# iiitduino_copy.net
KiCad netlist of a schematic drawn in EAGLE
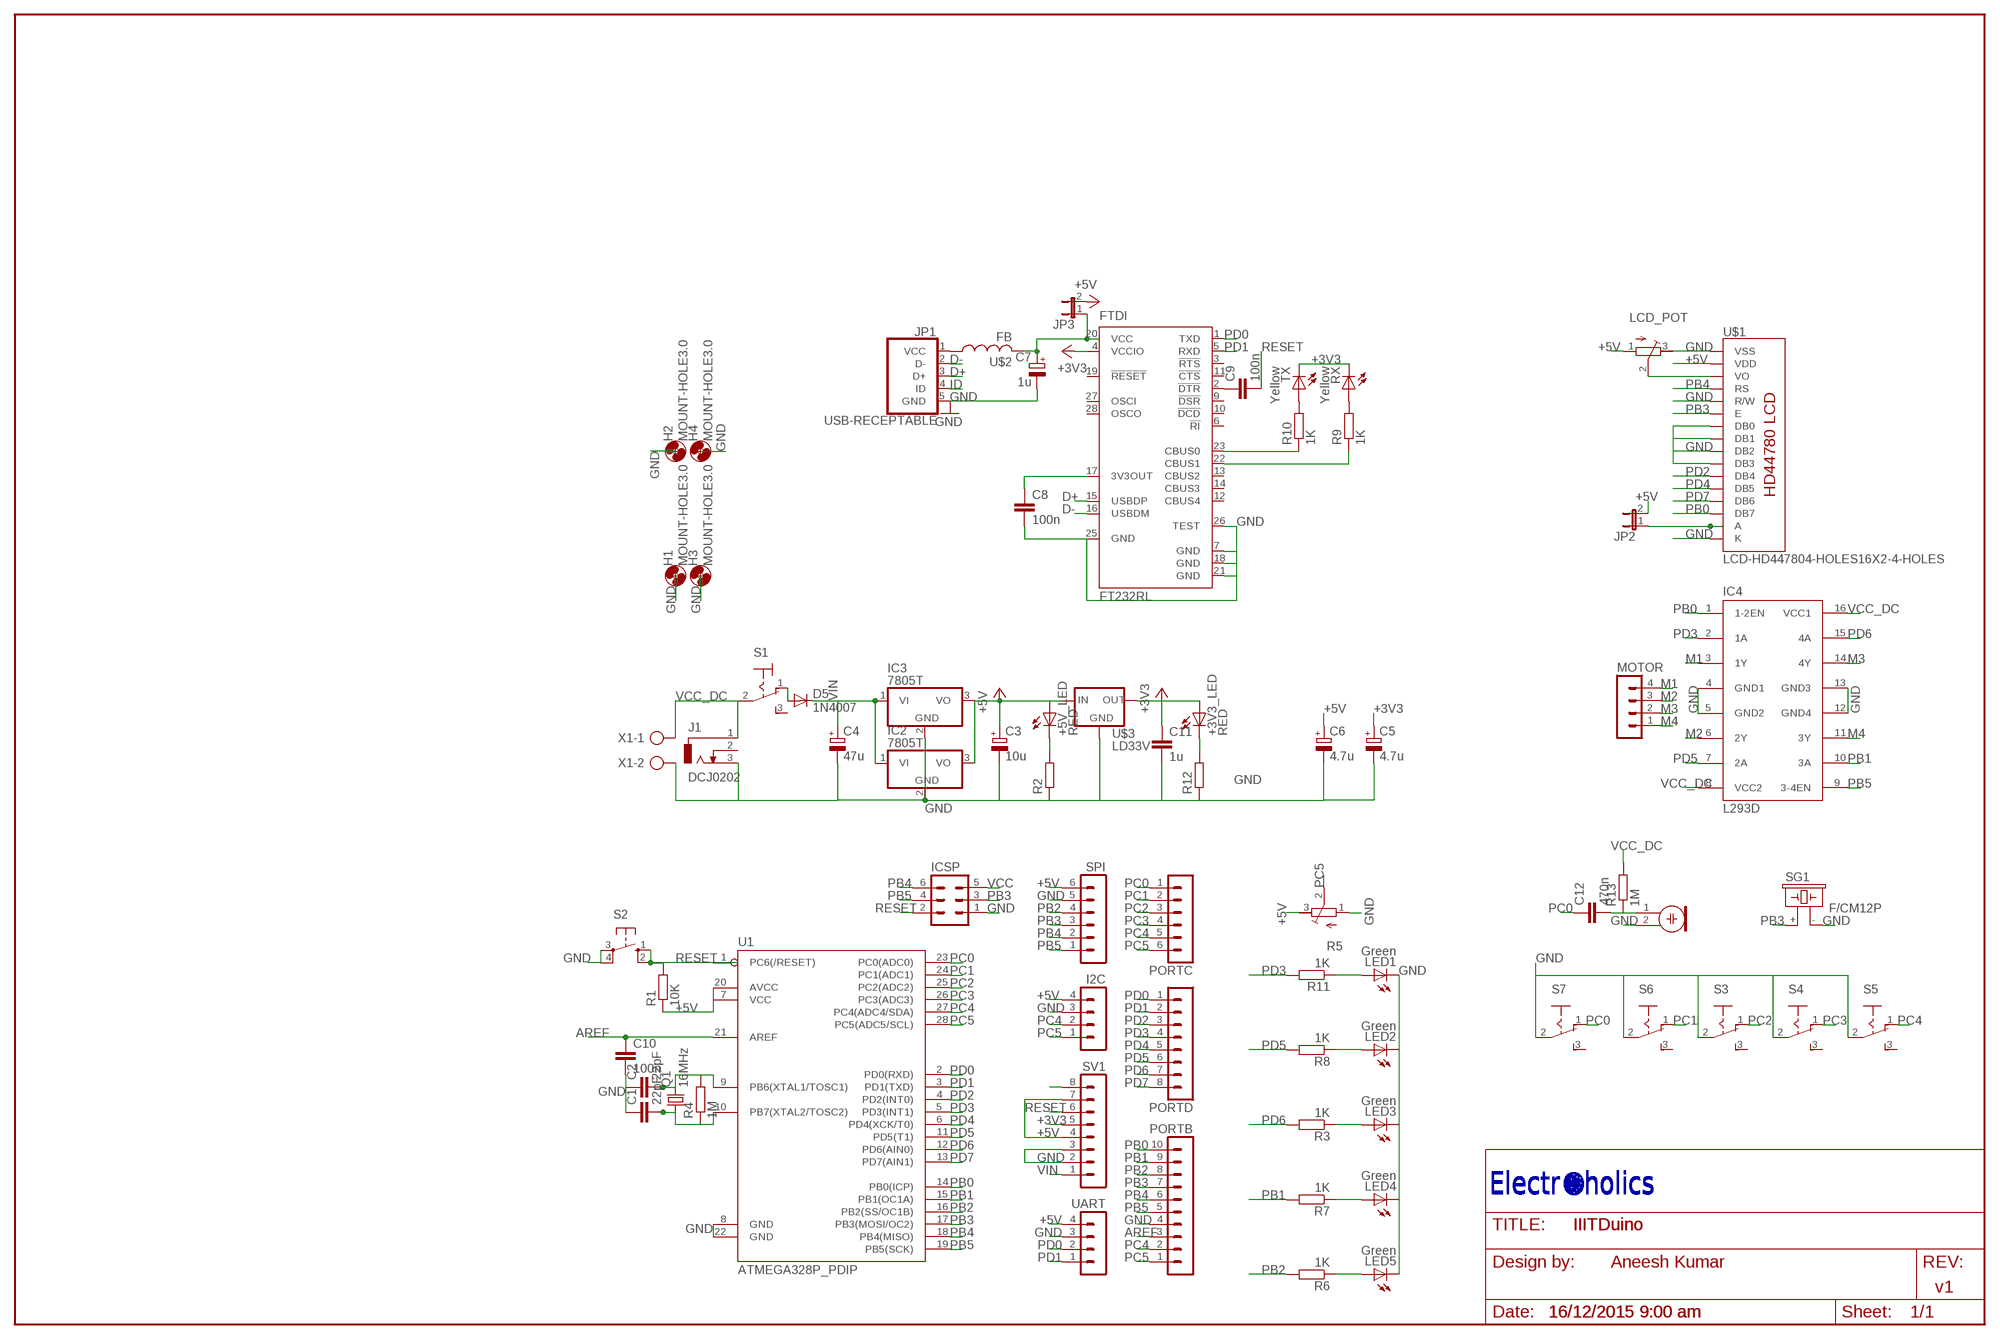
[diagram p0: schematic, sheet 1]

(export (version "E")
  (design (tool "Eeschema 10.0.6"))
  (components
    (comp (ref "+3V3_LED")
      (value "RED")
      (footprint "eagle-import:LED3MM")
      (libsource (lib "eagle-import") (part "LED3MM"))
    )
    (comp (ref "+5V_LED")
      (value "RED")
      (footprint "eagle-import:LED3MM")
      (libsource (lib "eagle-import") (part "LED3MM"))
    )
    (comp (ref "C1")
      (value "22pF")
      (footprint "eagle-import:C025-025X050")
      (libsource (lib "eagle-import") (part "C-EU025-025X050"))
    )
    (comp (ref "C2")
      (value "22pF")
      (footprint "eagle-import:C025-025X050")
      (libsource (lib "eagle-import") (part "C-EU025-025X050"))
    )
    (comp (ref "C3")
      (value "10u")
      (footprint "eagle-import:E2,5-6")
      (libsource (lib "eagle-import") (part "CPOL-EUE2.5-6"))
    )
    (comp (ref "C4")
      (value "47u")
      (footprint "eagle-import:E5-10,5")
      (libsource (lib "eagle-import") (part "CPOL-EUE5-10.5"))
    )
    (comp (ref "C5")
      (value "4.7u")
      (footprint "eagle-import:E2,5-6")
      (libsource (lib "eagle-import") (part "CPOL-EUE2.5-6"))
    )
    (comp (ref "C6")
      (value "4.7u")
      (footprint "eagle-import:E2,5-6")
      (libsource (lib "eagle-import") (part "CPOL-EUE2.5-6"))
    )
    (comp (ref "C7")
      (value "1u")
      (footprint "eagle-import:E2,5-6")
      (libsource (lib "eagle-import") (part "CPOL-EUE2.5-6"))
    )
    (comp (ref "C8")
      (value "100n")
      (footprint "eagle-import:C025-025X050")
      (libsource (lib "eagle-import") (part "C-EU025-025X050"))
    )
    (comp (ref "C9")
      (value "100n")
      (footprint "eagle-import:C025-025X050")
      (libsource (lib "eagle-import") (part "C-EU025-025X050"))
    )
    (comp (ref "C10")
      (value "100n")
      (footprint "eagle-import:C025-025X050")
      (libsource (lib "eagle-import") (part "C-EU025-025X050"))
    )
    (comp (ref "C11")
      (value "1u")
      (footprint "eagle-import:C025-025X050")
      (libsource (lib "eagle-import") (part "C-EU025-025X050"))
    )
    (comp (ref "C12")
      (value "470n")
      (footprint "eagle-import:C025-025X050")
      (libsource (lib "eagle-import") (part "C-EU025-025X050"))
    )
    (comp (ref "D5")
      (value "1N4007")
      (footprint "eagle-import:DO41-10")
      (libsource (lib "eagle-import") (part "1N4004"))
    )
    (comp (ref "FTDI")
      (value "FT232RL")
      (footprint "eagle-import:SSOP28")
      (libsource (lib "eagle-import") (part "FT232RL"))
    )
    (comp (ref "H1")
      (value "MOUNT-HOLE3.0")
      (footprint "eagle-import:3,0")
      (libsource (lib "eagle-import") (part "MOUNT-HOLE3.0"))
    )
    (comp (ref "H2")
      (value "MOUNT-HOLE3.0")
      (footprint "eagle-import:3,0")
      (libsource (lib "eagle-import") (part "MOUNT-HOLE3.0"))
    )
    (comp (ref "H3")
      (value "MOUNT-HOLE3.0")
      (footprint "eagle-import:3,0")
      (libsource (lib "eagle-import") (part "MOUNT-HOLE3.0"))
    )
    (comp (ref "H4")
      (value "MOUNT-HOLE3.0")
      (footprint "eagle-import:3,0")
      (libsource (lib "eagle-import") (part "MOUNT-HOLE3.0"))
    )
    (comp (ref "I2C")
      (value "MA04-1")
      (footprint "eagle-import:MA04-1")
      (libsource (lib "eagle-import") (part "MA04-1"))
    )
    (comp (ref "IC2")
      (value "7805T")
      (footprint "eagle-import:TO220H")
      (libsource (lib "eagle-import") (part "78T05"))
    )
    (comp (ref "IC3")
      (value "7805T")
      (footprint "eagle-import:TO220H")
      (libsource (lib "eagle-import") (part "78T05"))
    )
    (comp (ref "IC4")
      (value "L293D")
      (footprint "eagle-import:DIL16")
      (libsource (lib "eagle-import") (part "L293D"))
    )
    (comp (ref "ICSP")
      (value "MA03-2")
      (footprint "eagle-import:MA03-2")
      (libsource (lib "eagle-import") (part "MA03-2"))
    )
    (comp (ref "J1")
      (value "DCJ0202")
      (footprint "eagle-import:DCJ0202")
      (libsource (lib "eagle-import") (part "DCJ0202"))
    )
    (comp (ref "JP1")
      (value "USB-RECEPTABLE")
      (footprint "eagle-import:FCI-10103594-0001LF")
      (libsource (lib "eagle-import") (part "USB-RECEPTABLE"))
    )
    (comp (ref "JP2")
      (value "JP1E")
      (footprint "eagle-import:JP1")
      (libsource (lib "eagle-import") (part "JP1E"))
    )
    (comp (ref "JP3")
      (value "JP1E")
      (footprint "eagle-import:JP1")
      (libsource (lib "eagle-import") (part "JP1E"))
    )
    (comp (ref "LCD_POT")
      (value "R-TRIMM64W")
      (footprint "eagle-import:RTRIM64W")
      (libsource (lib "eagle-import") (part "R-TRIMM64W"))
    )
    (comp (ref "LED1")
      (value "Green")
      (footprint "eagle-import:LED3MM")
      (libsource (lib "eagle-import") (part "LED3MM"))
    )
    (comp (ref "LED2")
      (value "Green")
      (footprint "eagle-import:LED3MM")
      (libsource (lib "eagle-import") (part "LED3MM"))
    )
    (comp (ref "LED3")
      (value "Green")
      (footprint "eagle-import:LED3MM")
      (libsource (lib "eagle-import") (part "LED3MM"))
    )
    (comp (ref "LED4")
      (value "Green")
      (footprint "eagle-import:LED3MM")
      (libsource (lib "eagle-import") (part "LED3MM"))
    )
    (comp (ref "LED5")
      (value "Green")
      (footprint "eagle-import:LED3MM")
      (libsource (lib "eagle-import") (part "LED3MM"))
    )
    (comp (ref "M1")
      (value "ELECTRET_MICROPHON-F6050AP")
      (footprint "eagle-import:F6050AP")
      (libsource (lib "eagle-import") (part "ELECTRET_MICROPHON-F6050AP"))
    )
    (comp (ref "MOTOR")
      (value "MA04-1")
      (footprint "eagle-import:MA04-1")
      (libsource (lib "eagle-import") (part "MA04-1"))
    )
    (comp (ref "PORTB")
      (value "MA10-1W")
      (footprint "eagle-import:MA10-1W")
      (libsource (lib "eagle-import") (part "MA10-1W"))
    )
    (comp (ref "PORTC")
      (value "MA06-1")
      (footprint "eagle-import:MA06-1")
      (libsource (lib "eagle-import") (part "MA06-1"))
    )
    (comp (ref "PORTD")
      (value "MA08-1")
      (footprint "eagle-import:MA08-1")
      (libsource (lib "eagle-import") (part "MA08-1"))
    )
    (comp (ref "Q1")
      (value "16MHz")
      (footprint "eagle-import:HC49U70")
      (libsource (lib "eagle-import") (part "CRYSTALHC49U70"))
    )
    (comp (ref "R1")
      (value "10K")
      (footprint "eagle-import:0207_10")
      (libsource (lib "eagle-import") (part "R-EU_0207/10"))
    )
    (comp (ref "R2")
      (value "R-EU_0207/7")
      (footprint "eagle-import:0207_7")
      (libsource (lib "eagle-import") (part "R-EU_0207/7"))
    )
    (comp (ref "R3")
      (value "1K")
      (footprint "eagle-import:0207_10")
      (libsource (lib "eagle-import") (part "R-EU_0207/10"))
    )
    (comp (ref "R4")
      (value "1M")
      (footprint "eagle-import:0207_10")
      (libsource (lib "eagle-import") (part "R-EU_0207/10"))
    )
    (comp (ref "R5")
      (value "R-TRIMM64W")
      (footprint "eagle-import:RTRIM64W")
      (libsource (lib "eagle-import") (part "R-TRIMM64W"))
    )
    (comp (ref "R6")
      (value "1K")
      (footprint "eagle-import:0207_10")
      (libsource (lib "eagle-import") (part "R-EU_0207/10"))
    )
    (comp (ref "R7")
      (value "1K")
      (footprint "eagle-import:0207_10")
      (libsource (lib "eagle-import") (part "R-EU_0207/10"))
    )
    (comp (ref "R8")
      (value "1K")
      (footprint "eagle-import:0207_10")
      (libsource (lib "eagle-import") (part "R-EU_0207/10"))
    )
    (comp (ref "R9")
      (value "1K")
      (footprint "eagle-import:0207_7")
      (libsource (lib "eagle-import") (part "R-EU_0207/7"))
    )
    (comp (ref "R10")
      (value "1K")
      (footprint "eagle-import:0207_7")
      (libsource (lib "eagle-import") (part "R-EU_0207/7"))
    )
    (comp (ref "R11")
      (value "1K")
      (footprint "eagle-import:0207_10")
      (libsource (lib "eagle-import") (part "R-EU_0207/10"))
    )
    (comp (ref "R12")
      (value "R-EU_0207/7")
      (footprint "eagle-import:0207_7")
      (libsource (lib "eagle-import") (part "R-EU_0207/7"))
    )
    (comp (ref "R13")
      (value "1M")
      (footprint "eagle-import:0207_10")
      (libsource (lib "eagle-import") (part "R-EU_0207/10"))
    )
    (comp (ref "RX")
      (value "Yellow")
      (footprint "eagle-import:LED3MM")
      (libsource (lib "eagle-import") (part "LED3MM"))
    )
    (comp (ref "S1")
      (value "320-916")
      (footprint "eagle-import:320-916")
      (libsource (lib "eagle-import") (part "320-916"))
    )
    (comp (ref "S2")
      (value "10-XX")
      (footprint "eagle-import:B3F-10XX")
      (fields (field (name "MPN") "B3F-1000"))
      (libsource (lib "eagle-import") (part "10-XX"))
    )
    (comp (ref "S3")
      (value "255SB")
      (footprint "eagle-import:255SB")
      (libsource (lib "eagle-import") (part "255SB"))
    )
    (comp (ref "S4")
      (value "255SB")
      (footprint "eagle-import:255SB")
      (libsource (lib "eagle-import") (part "255SB"))
    )
    (comp (ref "S5")
      (value "255SB")
      (footprint "eagle-import:255SB")
      (libsource (lib "eagle-import") (part "255SB"))
    )
    (comp (ref "S6")
      (value "255SB")
      (footprint "eagle-import:255SB")
      (libsource (lib "eagle-import") (part "255SB"))
    )
    (comp (ref "S7")
      (value "255SB")
      (footprint "eagle-import:255SB")
      (libsource (lib "eagle-import") (part "255SB"))
    )
    (comp (ref "SG1")
      (value "F/CM12P")
      (footprint "eagle-import:F_CM12P")
      (libsource (lib "eagle-import") (part "F/CM12P"))
    )
    (comp (ref "SPI")
      (value "MA06-1")
      (footprint "eagle-import:MA06-1")
      (libsource (lib "eagle-import") (part "MA06-1"))
    )
    (comp (ref "SV1")
      (value "MA08-1")
      (footprint "eagle-import:MA08-1")
      (libsource (lib "eagle-import") (part "MA08-1"))
    )
    (comp (ref "TX")
      (value "Yellow")
      (footprint "eagle-import:LED3MM")
      (libsource (lib "eagle-import") (part "LED3MM"))
    )
    (comp (ref "U$1")
      (value "LCD-HD447804-HOLES16X2-4-HOLES")
      (footprint "eagle-import:LCD-16X2-4HOLES")
      (libsource (lib "eagle-import") (part "LCD-HD4478016X2-4-HOLES4-HOLES"))
    )
    (comp (ref "U$2") (value "FB") (footprint "eagle-import:FB") (libsource (lib "eagle-import") (part "FB")))
    (comp (ref "U$3")
      (value "LD33V")
      (footprint "eagle-import:TO-220")
      (libsource (lib "eagle-import") (part "LD33V"))
    )
    (comp (ref "U1")
      (value "ATMEGA328P_PDIP")
      (footprint "eagle-import:DIL28-3")
      (libsource (lib "eagle-import") (part "ATMEGA328P_PDIP"))
    )
    (comp (ref "UART")
      (value "MA04-1")
      (footprint "eagle-import:MA04-1")
      (libsource (lib "eagle-import") (part "MA04-1"))
    )
    (comp (ref "X1")
      (value "AK300/2")
      (footprint "eagle-import:AK300_2")
      (libsource (lib "eagle-import") (part "AK300/2"))
    )
  )
  (nets
    (net (code "1") (name "+3V3") (class "Default")
      (node (ref "+3V3_LED") (pin "A") (pinfunction "A_A") (pintype "passive"))
      (node (ref "C11") (pin "1") (pinfunction "1_1") (pintype "passive"))
      (node (ref "C5") (pin "+") (pinfunction "+_+") (pintype "passive"))
      (node (ref "FTDI") (pin "4") (pinfunction "VCCIO_4") (pintype "power_in"))
      (node (ref "RX") (pin "K") (pinfunction "C_K") (pintype "passive"))
      (node (ref "SV1") (pin "5") (pinfunction "5_5") (pintype "passive"))
      (node (ref "TX") (pin "K") (pinfunction "C_K") (pintype "passive"))
      (node (ref "U$3") (pin "2") (pinfunction "OUT_2") (pintype "passive"))
    )
    (net (code "2") (name "+5V") (class "Default")
      (node (ref "+5V_LED") (pin "A") (pinfunction "A_A") (pintype "passive"))
      (node (ref "C3") (pin "+") (pinfunction "+_+") (pintype "passive"))
      (node (ref "C6") (pin "+") (pinfunction "+_+") (pintype "passive"))
      (node (ref "C7") (pin "+") (pinfunction "+_+") (pintype "passive"))
      (node (ref "FTDI") (pin "20") (pinfunction "VCC_20") (pintype "power_in"))
      (node (ref "I2C") (pin "4") (pinfunction "4_4") (pintype "passive"))
      (node (ref "IC2") (pin "3") (pinfunction "VO_3") (pintype "passive"))
      (node (ref "IC3") (pin "3") (pinfunction "VO_3") (pintype "passive"))
      (node (ref "JP2") (pin "2") (pinfunction "2_2") (pintype "passive"))
      (node (ref "JP3") (pin "1") (pinfunction "1_1") (pintype "passive"))
      (node (ref "JP3") (pin "2") (pinfunction "2_2") (pintype "passive"))
      (node (ref "LCD_POT") (pin "1") (pinfunction "A_1") (pintype "passive"))
      (node (ref "R1") (pin "1") (pinfunction "1_1") (pintype "passive"))
      (node (ref "R5") (pin "3") (pinfunction "E_3") (pintype "passive"))
      (node (ref "SPI") (pin "6") (pinfunction "6_6") (pintype "passive"))
      (node (ref "SV1") (pin "4") (pinfunction "4_4") (pintype "passive"))
      (node (ref "SV1") (pin "7") (pinfunction "7_7") (pintype "passive"))
      (node (ref "U$1") (pin "2") (pinfunction "VDD_2") (pintype "power_in"))
      (node (ref "U$2") (pin "P$2") (pinfunction "2_P$2") (pintype "passive"))
      (node (ref "U$3") (pin "3") (pinfunction "IN_3") (pintype "input"))
      (node (ref "U1") (pin "20") (pinfunction "AVCC_20") (pintype "bidirectional"))
      (node (ref "U1") (pin "7") (pinfunction "VCC_7") (pintype "bidirectional"))
      (node (ref "UART") (pin "4") (pinfunction "4_4") (pintype "passive"))
    )
    (net (code "3") (name "/AREF") (class "Default")
      (node (ref "C10") (pin "1") (pinfunction "1_1") (pintype "passive"))
      (node (ref "PORTB") (pin "3") (pinfunction "3_3") (pintype "passive"))
      (node (ref "U1") (pin "21") (pinfunction "AREF_21") (pintype "bidirectional"))
    )
    (net (code "4") (name "/D+") (class "Default")
      (node (ref "FTDI") (pin "15") (pinfunction "USBDP_15") (pintype "bidirectional"))
      (node (ref "JP1") (pin "3") (pinfunction "D+_3") (pintype "bidirectional"))
    )
    (net (code "5") (name "/D-") (class "Default")
      (node (ref "FTDI") (pin "16") (pinfunction "USBDM_16") (pintype "bidirectional"))
      (node (ref "JP1") (pin "2") (pinfunction "D-_2") (pintype "bidirectional"))
    )
    (net (code "6") (name "/ID") (class "Default")
      (node (ref "JP1") (pin "4") (pinfunction "ID_4") (pintype "bidirectional"))
    )
    (net (code "7") (name "/M1") (class "Default")
      (node (ref "IC4") (pin "3") (pinfunction "1Y_3") (pintype "output"))
      (node (ref "MOTOR") (pin "4") (pinfunction "4_4") (pintype "passive"))
    )
    (net (code "8") (name "/M2") (class "Default")
      (node (ref "IC4") (pin "6") (pinfunction "2Y_6") (pintype "output"))
      (node (ref "MOTOR") (pin "3") (pinfunction "3_3") (pintype "passive"))
    )
    (net (code "9") (name "/M3") (class "Default")
      (node (ref "IC4") (pin "14") (pinfunction "4Y_14") (pintype "output"))
      (node (ref "MOTOR") (pin "2") (pinfunction "2_2") (pintype "passive"))
    )
    (net (code "10") (name "/M4") (class "Default")
      (node (ref "IC4") (pin "11") (pinfunction "3Y_11") (pintype "output"))
      (node (ref "MOTOR") (pin "1") (pinfunction "1_1") (pintype "passive"))
    )
    (net (code "11") (name "/PB0") (class "Default")
      (node (ref "IC4") (pin "1") (pinfunction "1-2EN_1") (pintype "input"))
      (node (ref "PORTB") (pin "10") (pinfunction "10_10") (pintype "passive"))
      (node (ref "U$1") (pin "14") (pinfunction "DB7_14") (pintype "bidirectional"))
      (node (ref "U1") (pin "14") (pinfunction "PB0(ICP)_14") (pintype "bidirectional"))
    )
    (net (code "12") (name "/PB1") (class "Default")
      (node (ref "IC4") (pin "10") (pinfunction "3A_10") (pintype "input"))
      (node (ref "PORTB") (pin "9") (pinfunction "9_9") (pintype "passive"))
      (node (ref "R7") (pin "2") (pinfunction "2_2") (pintype "passive"))
      (node (ref "U1") (pin "15") (pinfunction "PB1(OC1A)_15") (pintype "bidirectional"))
    )
    (net (code "13") (name "/PB2") (class "Default")
      (node (ref "PORTB") (pin "8") (pinfunction "8_8") (pintype "passive"))
      (node (ref "R6") (pin "2") (pinfunction "2_2") (pintype "passive"))
      (node (ref "SPI") (pin "4") (pinfunction "4_4") (pintype "passive"))
      (node (ref "U1") (pin "16") (pinfunction "PB2(SS/OC1B)_16") (pintype "bidirectional"))
    )
    (net (code "14") (name "/PB3") (class "Default")
      (node (ref "ICSP") (pin "3") (pinfunction "3_3") (pintype "passive"))
      (node (ref "PORTB") (pin "7") (pinfunction "7_7") (pintype "passive"))
      (node (ref "SG1") (pin "+") (pinfunction "1_+") (pintype "passive"))
      (node (ref "SPI") (pin "3") (pinfunction "3_3") (pintype "passive"))
      (node (ref "U$1") (pin "6") (pinfunction "E_6") (pintype "input"))
      (node (ref "U1") (pin "17") (pinfunction "PB3(MOSI/OC2)_17") (pintype "bidirectional"))
    )
    (net (code "15") (name "/PB4") (class "Default")
      (node (ref "ICSP") (pin "6") (pinfunction "6_6") (pintype "passive"))
      (node (ref "PORTB") (pin "6") (pinfunction "6_6") (pintype "passive"))
      (node (ref "SPI") (pin "2") (pinfunction "2_2") (pintype "passive"))
      (node (ref "U$1") (pin "4") (pinfunction "RS_4") (pintype "input"))
      (node (ref "U1") (pin "18") (pinfunction "PB4(MISO)_18") (pintype "bidirectional"))
    )
    (net (code "16") (name "/PB5") (class "Default")
      (node (ref "IC4") (pin "9") (pinfunction "3-4EN_9") (pintype "input"))
      (node (ref "ICSP") (pin "4") (pinfunction "4_4") (pintype "passive"))
      (node (ref "PORTB") (pin "5") (pinfunction "5_5") (pintype "passive"))
      (node (ref "SPI") (pin "1") (pinfunction "1_1") (pintype "passive"))
      (node (ref "U1") (pin "19") (pinfunction "PB5(SCK)_19") (pintype "bidirectional"))
    )
    (net (code "17") (name "/PC0") (class "Default")
      (node (ref "C12") (pin "1") (pinfunction "1_1") (pintype "passive"))
      (node (ref "PORTC") (pin "1") (pinfunction "1_1") (pintype "passive"))
      (node (ref "S7") (pin "1") (pinfunction "O_1") (pintype "passive"))
      (node (ref "U1") (pin "23") (pinfunction "PC0(ADC0)_23") (pintype "bidirectional"))
    )
    (net (code "18") (name "/PC1") (class "Default")
      (node (ref "PORTC") (pin "2") (pinfunction "2_2") (pintype "passive"))
      (node (ref "S6") (pin "1") (pinfunction "O_1") (pintype "passive"))
      (node (ref "U1") (pin "24") (pinfunction "PC1(ADC1)_24") (pintype "bidirectional"))
    )
    (net (code "19") (name "/PC2") (class "Default")
      (node (ref "PORTC") (pin "3") (pinfunction "3_3") (pintype "passive"))
      (node (ref "S3") (pin "1") (pinfunction "O_1") (pintype "passive"))
      (node (ref "U1") (pin "25") (pinfunction "PC2(ADC2)_25") (pintype "bidirectional"))
    )
    (net (code "20") (name "/PC3") (class "Default")
      (node (ref "PORTC") (pin "4") (pinfunction "4_4") (pintype "passive"))
      (node (ref "S4") (pin "1") (pinfunction "O_1") (pintype "passive"))
      (node (ref "U1") (pin "26") (pinfunction "PC3(ADC3)_26") (pintype "bidirectional"))
    )
    (net (code "21") (name "/PC4") (class "Default")
      (node (ref "I2C") (pin "2") (pinfunction "2_2") (pintype "passive"))
      (node (ref "PORTB") (pin "2") (pinfunction "2_2") (pintype "passive"))
      (node (ref "PORTC") (pin "5") (pinfunction "5_5") (pintype "passive"))
      (node (ref "S5") (pin "1") (pinfunction "O_1") (pintype "passive"))
      (node (ref "U1") (pin "27") (pinfunction "PC4(ADC4/SDA)_27") (pintype "bidirectional"))
    )
    (net (code "22") (name "/PC5") (class "Default")
      (node (ref "I2C") (pin "1") (pinfunction "1_1") (pintype "passive"))
      (node (ref "PORTB") (pin "1") (pinfunction "1_1") (pintype "passive"))
      (node (ref "PORTC") (pin "6") (pinfunction "6_6") (pintype "passive"))
      (node (ref "R5") (pin "2") (pinfunction "S_2") (pintype "passive"))
      (node (ref "U1") (pin "28") (pinfunction "PC5(ADC5/SCL)_28") (pintype "bidirectional"))
    )
    (net (code "23") (name "/PD0") (class "Default")
      (node (ref "FTDI") (pin "1") (pinfunction "TXD_1") (pintype "output"))
      (node (ref "PORTD") (pin "1") (pinfunction "1_1") (pintype "passive"))
      (node (ref "U1") (pin "2") (pinfunction "PD0(RXD)_2") (pintype "bidirectional"))
      (node (ref "UART") (pin "2") (pinfunction "2_2") (pintype "passive"))
    )
    (net (code "24") (name "/PD1") (class "Default")
      (node (ref "FTDI") (pin "5") (pinfunction "RXD_5") (pintype "input"))
      (node (ref "PORTD") (pin "2") (pinfunction "2_2") (pintype "passive"))
      (node (ref "U1") (pin "3") (pinfunction "PD1(TXD)_3") (pintype "bidirectional"))
      (node (ref "UART") (pin "1") (pinfunction "1_1") (pintype "passive"))
    )
    (net (code "25") (name "/PD2") (class "Default")
      (node (ref "PORTD") (pin "3") (pinfunction "3_3") (pintype "passive"))
      (node (ref "U$1") (pin "11") (pinfunction "DB4_11") (pintype "bidirectional"))
      (node (ref "U1") (pin "4") (pinfunction "PD2(INT0)_4") (pintype "bidirectional"))
    )
    (net (code "26") (name "/PD3") (class "Default")
      (node (ref "IC4") (pin "2") (pinfunction "1A_2") (pintype "input"))
      (node (ref "PORTD") (pin "4") (pinfunction "4_4") (pintype "passive"))
      (node (ref "R11") (pin "2") (pinfunction "2_2") (pintype "passive"))
      (node (ref "U1") (pin "5") (pinfunction "PD3(INT1)_5") (pintype "bidirectional"))
    )
    (net (code "27") (name "/PD4") (class "Default")
      (node (ref "PORTD") (pin "5") (pinfunction "5_5") (pintype "passive"))
      (node (ref "U$1") (pin "12") (pinfunction "DB5_12") (pintype "bidirectional"))
      (node (ref "U1") (pin "6") (pinfunction "PD4(XCK/T0)_6") (pintype "bidirectional"))
    )
    (net (code "28") (name "/PD5") (class "Default")
      (node (ref "IC4") (pin "7") (pinfunction "2A_7") (pintype "input"))
      (node (ref "PORTD") (pin "6") (pinfunction "6_6") (pintype "passive"))
      (node (ref "R8") (pin "2") (pinfunction "2_2") (pintype "passive"))
      (node (ref "U1") (pin "11") (pinfunction "PD5(T1)_11") (pintype "bidirectional"))
    )
    (net (code "29") (name "/PD6") (class "Default")
      (node (ref "IC4") (pin "15") (pinfunction "4A_15") (pintype "input"))
      (node (ref "PORTD") (pin "7") (pinfunction "7_7") (pintype "passive"))
      (node (ref "R3") (pin "2") (pinfunction "2_2") (pintype "passive"))
      (node (ref "U1") (pin "12") (pinfunction "PD6(AIN0)_12") (pintype "bidirectional"))
    )
    (net (code "30") (name "/PD7") (class "Default")
      (node (ref "PORTD") (pin "8") (pinfunction "8_8") (pintype "passive"))
      (node (ref "U$1") (pin "13") (pinfunction "DB6_13") (pintype "bidirectional"))
      (node (ref "U1") (pin "13") (pinfunction "PD7(AIN1)_13") (pintype "bidirectional"))
    )
    (net (code "31") (name "/RESET") (class "Default")
      (node (ref "C9") (pin "2") (pinfunction "2_2") (pintype "passive"))
      (node (ref "ICSP") (pin "2") (pinfunction "2_2") (pintype "passive"))
      (node (ref "R1") (pin "2") (pinfunction "2_2") (pintype "passive"))
      (node (ref "S2") (pin "1") (pinfunction "S_1") (pintype "passive"))
      (node (ref "S2") (pin "2") (pinfunction "S1_2") (pintype "passive"))
      (node (ref "SV1") (pin "6") (pinfunction "6_6") (pintype "passive"))
    )
    (net (code "32") (name "/VCC") (class "Default")
      (node (ref "ICSP") (pin "5") (pinfunction "5_5") (pintype "passive"))
    )
    (net (code "33") (name "/VCC_DC") (class "Default")
      (node (ref "IC4") (pin "16") (pinfunction "VCC1_16") (pintype "power_in"))
      (node (ref "IC4") (pin "8") (pinfunction "VCC2_8") (pintype "power_in"))
      (node (ref "J1") (pin "1") (pinfunction "1_1") (pintype "passive"))
      (node (ref "R13") (pin "2") (pinfunction "2_2") (pintype "passive"))
      (node (ref "S1") (pin "2") (pinfunction "P_2") (pintype "passive"))
      (node (ref "X1") (pin "1") (pinfunction "KL_1") (pintype "passive"))
    )
    (net (code "34") (name "/VIN") (class "Default")
      (node (ref "C4") (pin "+") (pinfunction "+_+") (pintype "passive"))
      (node (ref "D5") (pin "C") (pinfunction "C_C") (pintype "passive"))
      (node (ref "IC2") (pin "1") (pinfunction "VI_1") (pintype "input"))
      (node (ref "IC3") (pin "1") (pinfunction "VI_1") (pintype "input"))
      (node (ref "SV1") (pin "1") (pinfunction "1_1") (pintype "passive"))
    )
    (net (code "35") (name "GND") (class "Default")
      (node (ref "C1") (pin "1") (pinfunction "1_1") (pintype "passive"))
      (node (ref "C10") (pin "2") (pinfunction "2_2") (pintype "passive"))
      (node (ref "C11") (pin "2") (pinfunction "2_2") (pintype "passive"))
      (node (ref "C2") (pin "1") (pinfunction "1_1") (pintype "passive"))
      (node (ref "C3") (pin "-") (pinfunction "-_-") (pintype "passive"))
      (node (ref "C4") (pin "-") (pinfunction "-_-") (pintype "passive"))
      (node (ref "C5") (pin "-") (pinfunction "-_-") (pintype "passive"))
      (node (ref "C6") (pin "-") (pinfunction "-_-") (pintype "passive"))
      (node (ref "C7") (pin "-") (pinfunction "-_-") (pintype "passive"))
      (node (ref "C8") (pin "2") (pinfunction "2_2") (pintype "passive"))
      (node (ref "FTDI") (pin "18") (pinfunction "GND_18") (pintype "power_in"))
      (node (ref "FTDI") (pin "21") (pinfunction "GND_21") (pintype "power_in"))
      (node (ref "FTDI") (pin "25") (pinfunction "GND_25") (pintype "power_in"))
      (node (ref "FTDI") (pin "26") (pinfunction "TEST_26") (pintype "input"))
      (node (ref "FTDI") (pin "7") (pinfunction "GND_7") (pintype "power_in"))
      (node (ref "I2C") (pin "3") (pinfunction "3_3") (pintype "passive"))
      (node (ref "IC2") (pin "2") (pinfunction "GND_2") (pintype "passive"))
      (node (ref "IC3") (pin "2") (pinfunction "GND_2") (pintype "passive"))
      (node (ref "IC4") (pin "12") (pinfunction "GND4_12") (pintype "power_in"))
      (node (ref "IC4") (pin "13") (pinfunction "GND3_13") (pintype "power_in"))
      (node (ref "IC4") (pin "4") (pinfunction "GND1_4") (pintype "power_in"))
      (node (ref "IC4") (pin "5") (pinfunction "GND2_5") (pintype "power_in"))
      (node (ref "ICSP") (pin "1") (pinfunction "1_1") (pintype "passive"))
      (node (ref "J1") (pin "3") (pinfunction "3_3") (pintype "passive"))
      (node (ref "JP1") (pin "5") (pinfunction "GND_5") (pintype "bidirectional"))
      (node (ref "LCD_POT") (pin "3") (pinfunction "E_3") (pintype "passive"))
      (node (ref "LED1") (pin "K") (pinfunction "C_K") (pintype "passive"))
      (node (ref "LED2") (pin "K") (pinfunction "C_K") (pintype "passive"))
      (node (ref "LED3") (pin "K") (pinfunction "C_K") (pintype "passive"))
      (node (ref "LED4") (pin "K") (pinfunction "C_K") (pintype "passive"))
      (node (ref "LED5") (pin "K") (pinfunction "C_K") (pintype "passive"))
      (node (ref "M1") (pin "2") (pinfunction "2_2") (pintype "passive"))
      (node (ref "PORTB") (pin "4") (pinfunction "4_4") (pintype "passive"))
      (node (ref "R12") (pin "1") (pinfunction "1_1") (pintype "passive"))
      (node (ref "R2") (pin "1") (pinfunction "1_1") (pintype "passive"))
      (node (ref "R5") (pin "1") (pinfunction "A_1") (pintype "passive"))
      (node (ref "S2") (pin "3") (pinfunction "P_3") (pintype "passive"))
      (node (ref "S2") (pin "4") (pinfunction "P1_4") (pintype "passive"))
      (node (ref "S3") (pin "2") (pinfunction "P_2") (pintype "passive"))
      (node (ref "S4") (pin "2") (pinfunction "P_2") (pintype "passive"))
      (node (ref "S5") (pin "2") (pinfunction "P_2") (pintype "passive"))
      (node (ref "S6") (pin "2") (pinfunction "P_2") (pintype "passive"))
      (node (ref "S7") (pin "2") (pinfunction "P_2") (pintype "passive"))
      (node (ref "SG1") (pin "-") (pinfunction "2_-") (pintype "passive"))
      (node (ref "SPI") (pin "5") (pinfunction "5_5") (pintype "passive"))
      (node (ref "SV1") (pin "2") (pinfunction "2_2") (pintype "passive"))
      (node (ref "SV1") (pin "3") (pinfunction "3_3") (pintype "passive"))
      (node (ref "U$1") (pin "1") (pinfunction "VSS_1") (pintype "power_in"))
      (node (ref "U$1") (pin "10") (pinfunction "DB3_10") (pintype "bidirectional"))
      (node (ref "U$1") (pin "16") (pinfunction "K_16") (pintype "power_in"))
      (node (ref "U$1") (pin "5") (pinfunction "R/W_5") (pintype "input"))
      (node (ref "U$1") (pin "7") (pinfunction "DB0_7") (pintype "bidirectional"))
      (node (ref "U$1") (pin "8") (pinfunction "DB1_8") (pintype "bidirectional"))
      (node (ref "U$1") (pin "9") (pinfunction "DB2_9") (pintype "bidirectional"))
      (node (ref "U$3") (pin "1") (pinfunction "GND_1") (pintype "input"))
      (node (ref "U1") (pin "22") (pinfunction "GND_22") (pintype "bidirectional"))
      (node (ref "U1") (pin "8") (pinfunction "GND_8") (pintype "bidirectional"))
      (node (ref "UART") (pin "3") (pinfunction "3_3") (pintype "passive"))
      (node (ref "X1") (pin "2") (pinfunction "KL_2") (pintype "passive"))
    )
    (net (code "36") (name "Net-(+3V3_LED-C)") (class "Default")
      (node (ref "+3V3_LED") (pin "K") (pinfunction "C_K") (pintype "passive"))
      (node (ref "R12") (pin "2") (pinfunction "2_2") (pintype "passive"))
    )
    (net (code "37") (name "Net-(+5V_LED-C)") (class "Default")
      (node (ref "+5V_LED") (pin "K") (pinfunction "C_K") (pintype "passive"))
      (node (ref "R2") (pin "2") (pinfunction "2_2") (pintype "passive"))
    )
    (net (code "38") (name "Net-(C12-Pad2)") (class "Default")
      (node (ref "C12") (pin "2") (pinfunction "2_2") (pintype "passive"))
      (node (ref "M1") (pin "1") (pinfunction "1_1") (pintype "passive"))
      (node (ref "R13") (pin "1") (pinfunction "1_1") (pintype "passive"))
    )
    (net (code "39") (name "Net-(FTDI-3V3OUT)") (class "Default")
      (node (ref "C8") (pin "1") (pinfunction "1_1") (pintype "passive"))
      (node (ref "FTDI") (pin "17") (pinfunction "3V3OUT_17") (pintype "output"))
    )
    (net (code "40") (name "Net-(FTDI-CBUS0)") (class "Default")
      (node (ref "FTDI") (pin "23") (pinfunction "CBUS0_23") (pintype "bidirectional"))
      (node (ref "R10") (pin "1") (pinfunction "1_1") (pintype "passive"))
    )
    (net (code "41") (name "Net-(FTDI-CBUS1)") (class "Default")
      (node (ref "FTDI") (pin "22") (pinfunction "CBUS1_22") (pintype "bidirectional"))
      (node (ref "R9") (pin "1") (pinfunction "1_1") (pintype "passive"))
    )
    (net (code "42") (name "Net-(FTDI-~{DTR})") (class "Default")
      (node (ref "C9") (pin "1") (pinfunction "1_1") (pintype "passive"))
      (node (ref "FTDI") (pin "2") (pinfunction "~{DTR}_2") (pintype "output"))
    )
    (net (code "43") (name "Net-(JP1-VCC)") (class "Default")
      (node (ref "JP1") (pin "1") (pinfunction "VCC_1") (pintype "bidirectional"))
      (node (ref "U$2") (pin "P$1") (pinfunction "1_P$1") (pintype "passive"))
    )
    (net (code "44") (name "Net-(LCD_POT-S)") (class "Default")
      (node (ref "LCD_POT") (pin "2") (pinfunction "S_2") (pintype "passive"))
      (node (ref "U$1") (pin "3") (pinfunction "VO_3") (pintype "bidirectional"))
    )
    (net (code "45") (name "Net-(LED1-PadA)") (class "Default")
      (node (ref "LED1") (pin "A") (pinfunction "A_A") (pintype "passive"))
      (node (ref "R11") (pin "1") (pinfunction "1_1") (pintype "passive"))
    )
    (net (code "46") (name "Net-(LED2-PadA)") (class "Default")
      (node (ref "LED2") (pin "A") (pinfunction "A_A") (pintype "passive"))
      (node (ref "R8") (pin "1") (pinfunction "1_1") (pintype "passive"))
    )
    (net (code "47") (name "Net-(LED3-PadA)") (class "Default")
      (node (ref "LED3") (pin "A") (pinfunction "A_A") (pintype "passive"))
      (node (ref "R3") (pin "1") (pinfunction "1_1") (pintype "passive"))
    )
    (net (code "48") (name "Net-(LED4-PadA)") (class "Default")
      (node (ref "LED4") (pin "A") (pinfunction "A_A") (pintype "passive"))
      (node (ref "R7") (pin "1") (pinfunction "1_1") (pintype "passive"))
    )
    (net (code "49") (name "Net-(LED5-PadA)") (class "Default")
      (node (ref "LED5") (pin "A") (pinfunction "A_A") (pintype "passive"))
      (node (ref "R6") (pin "1") (pinfunction "1_1") (pintype "passive"))
    )
    (net (code "50") (name "Net-(R9-Pad2)") (class "Default")
      (node (ref "R9") (pin "2") (pinfunction "2_2") (pintype "passive"))
      (node (ref "RX") (pin "A") (pinfunction "A_A") (pintype "passive"))
    )
    (net (code "51") (name "Net-(R10-Pad2)") (class "Default")
      (node (ref "R10") (pin "2") (pinfunction "2_2") (pintype "passive"))
      (node (ref "TX") (pin "A") (pinfunction "A_A") (pintype "passive"))
    )
    (net (code "52") (name "Net-(S1-O)") (class "Default")
      (node (ref "D5") (pin "A") (pinfunction "A_A") (pintype "passive"))
      (node (ref "S1") (pin "1") (pinfunction "O_1") (pintype "passive"))
    )
    (net (code "53") (name "Net-(U$1-A)") (class "Default")
      (node (ref "JP2") (pin "1") (pinfunction "1_1") (pintype "passive"))
      (node (ref "U$1") (pin "15") (pinfunction "A_15") (pintype "power_in"))
    )
    (net (code "54") (name "Net-(U1-PB6(XTAL1{slash}TOSC1))") (class "Default")
      (node (ref "C2") (pin "2") (pinfunction "2_2") (pintype "passive"))
      (node (ref "Q1") (pin "2") (pinfunction "2_2") (pintype "passive"))
      (node (ref "R4") (pin "2") (pinfunction "2_2") (pintype "passive"))
      (node (ref "U1") (pin "9") (pinfunction "PB6(XTAL1/TOSC1)_9") (pintype "bidirectional"))
    )
    (net (code "55") (name "Net-(U1-PB7(XTAL2{slash}TOSC2))") (class "Default")
      (node (ref "C1") (pin "2") (pinfunction "2_2") (pintype "passive"))
      (node (ref "Q1") (pin "1") (pinfunction "1_1") (pintype "passive"))
      (node (ref "R4") (pin "1") (pinfunction "1_1") (pintype "passive"))
      (node (ref "U1") (pin "10") (pinfunction "PB7(XTAL2/TOSC2)_10") (pintype "bidirectional"))
    )
    (net (code "56") (name "unconnected-(FTDI-CBUS2-Pad13)") (class "Default")
      (node (ref "FTDI") (pin "13") (pinfunction "CBUS2_13") (pintype "bidirectional"))
    )
    (net (code "57") (name "unconnected-(FTDI-CBUS3-Pad14)") (class "Default")
      (node (ref "FTDI") (pin "14") (pinfunction "CBUS3_14") (pintype "bidirectional"))
    )
    (net (code "58") (name "unconnected-(FTDI-CBUS4-Pad12)") (class "Default")
      (node (ref "FTDI") (pin "12") (pinfunction "CBUS4_12") (pintype "bidirectional"))
    )
    (net (code "59") (name "unconnected-(FTDI-OSCI-Pad27)") (class "Default")
      (node (ref "FTDI") (pin "27") (pinfunction "OSCI_27") (pintype "input"))
    )
    (net (code "60") (name "unconnected-(FTDI-OSCO-Pad28)") (class "Default")
      (node (ref "FTDI") (pin "28") (pinfunction "OSCO_28") (pintype "output"))
    )
    (net (code "61") (name "unconnected-(FTDI-~{CTS}-Pad11)") (class "Default")
      (node (ref "FTDI") (pin "11") (pinfunction "~{CTS}_11") (pintype "input"))
    )
    (net (code "62") (name "unconnected-(FTDI-~{DCD}-Pad10)") (class "Default")
      (node (ref "FTDI") (pin "10") (pinfunction "~{DCD}_10") (pintype "input"))
    )
    (net (code "63") (name "unconnected-(FTDI-~{DSR}-Pad9)") (class "Default")
      (node (ref "FTDI") (pin "9") (pinfunction "~{DSR}_9") (pintype "input"))
    )
    (net (code "64") (name "unconnected-(FTDI-~{RESET}-Pad19)") (class "Default")
      (node (ref "FTDI") (pin "19") (pinfunction "~{RESET}_19") (pintype "input"))
    )
    (net (code "65") (name "unconnected-(FTDI-~{RI}-Pad6)") (class "Default")
      (node (ref "FTDI") (pin "6") (pinfunction "~{RI}_6") (pintype "input"))
    )
    (net (code "66") (name "unconnected-(FTDI-~{RTS}-Pad3)") (class "Default")
      (node (ref "FTDI") (pin "3") (pinfunction "~{RTS}_3") (pintype "output"))
    )
    (net (code "67") (name "unconnected-(J1-Pad2)") (class "Default")
      (node (ref "J1") (pin "2") (pinfunction "2_2") (pintype "passive"))
    )
    (net (code "68") (name "unconnected-(S1-S-Pad3)") (class "Default")
      (node (ref "S1") (pin "3") (pinfunction "S_3") (pintype "passive"))
    )
    (net (code "69") (name "unconnected-(S3-S-Pad3)") (class "Default")
      (node (ref "S3") (pin "3") (pinfunction "S_3") (pintype "passive"))
    )
    (net (code "70") (name "unconnected-(S4-S-Pad3)") (class "Default")
      (node (ref "S4") (pin "3") (pinfunction "S_3") (pintype "passive"))
    )
    (net (code "71") (name "unconnected-(S5-S-Pad3)") (class "Default")
      (node (ref "S5") (pin "3") (pinfunction "S_3") (pintype "passive"))
    )
    (net (code "72") (name "unconnected-(S6-S-Pad3)") (class "Default")
      (node (ref "S6") (pin "3") (pinfunction "S_3") (pintype "passive"))
    )
    (net (code "73") (name "unconnected-(S7-S-Pad3)") (class "Default")
      (node (ref "S7") (pin "3") (pinfunction "S_3") (pintype "passive"))
    )
    (net (code "74") (name "unconnected-(SV1-Pad8)") (class "Default")
      (node (ref "SV1") (pin "8") (pinfunction "8_8") (pintype "passive"))
    )
    (net (code "75") (name "unconnected-(U1-PC6({slash}RESET)-Pad1)") (class "Default")
      (node (ref "U1") (pin "1") (pinfunction "PC6(/RESET)_1") (pintype "bidirectional"))
    )
  )
)
